# Flow_sensor.net
KiCad netlist of a schematic drawn in Altium Designer
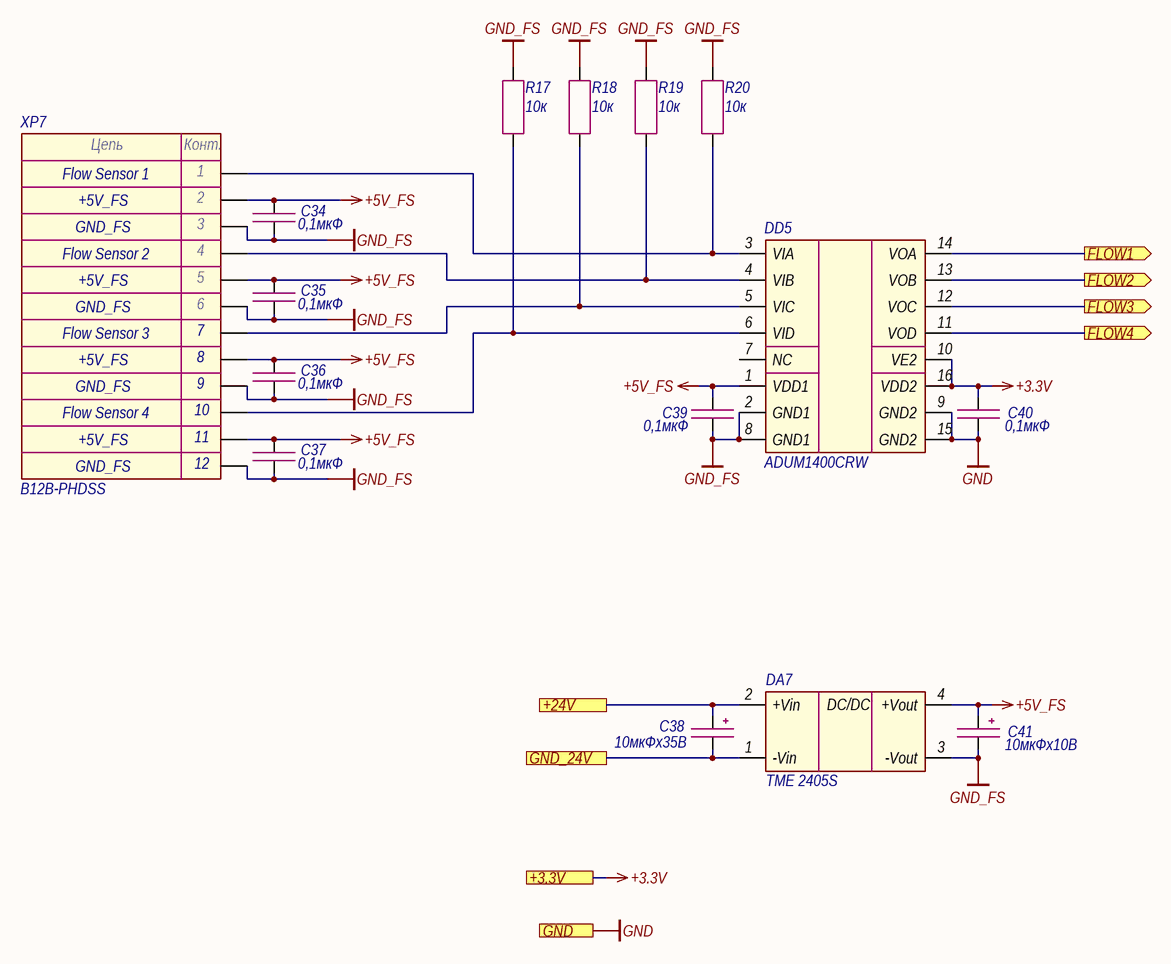
[diagram p0: Flow_sensor.SchDoc]

(export (version "E")
  (design (tool "Eeschema 10.0.6"))
  (components
    (comp (ref "C34")
      (value "0,1мкФ")
      (footprint "Pcb_library:CAP_0603")
      (fields (field (name "MANUFACTURER") "Murata"))
      (libsource (lib "Schem_library") (part "Capacitor"))
    )
    (comp (ref "C35")
      (value "0,1мкФ")
      (footprint "Pcb_library:CAP_0603")
      (fields (field (name "MANUFACTURER") "Murata"))
      (libsource (lib "Schem_library") (part "Capacitor"))
    )
    (comp (ref "C36")
      (value "0,1мкФ")
      (footprint "Pcb_library:CAP_0603")
      (fields (field (name "MANUFACTURER") "Murata"))
      (libsource (lib "Schem_library") (part "Capacitor"))
    )
    (comp (ref "C37")
      (value "0,1мкФ")
      (footprint "Pcb_library:CAP_0603")
      (fields (field (name "MANUFACTURER") "Murata"))
      (libsource (lib "Schem_library") (part "Capacitor"))
    )
    (comp (ref "C38")
      (value "10мкФх35B")
      (footprint "Pcb_library:CAP_C")
      (libsource (lib "Schem_library") (part "Capacitor_Polar"))
    )
    (comp (ref "C39")
      (value "0,1мкФ")
      (footprint "Pcb_library:CAP_0603")
      (fields (field (name "MANUFACTURER") "Murata"))
      (libsource (lib "Schem_library") (part "Capacitor"))
    )
    (comp (ref "C40")
      (value "0,1мкФ")
      (footprint "Pcb_library:CAP_0603")
      (fields (field (name "MANUFACTURER") "Murata"))
      (libsource (lib "Schem_library") (part "Capacitor"))
    )
    (comp (ref "C41")
      (value "10мкФх10B")
      (footprint "Pcb_library:CAP_A")
      (libsource (lib "Schem_library") (part "Capacitor_Polar"))
    )
    (comp (ref "DA7")
      (value "TME 2405S")
      (footprint "Pcb_library:TME (SIP-4)")
      (fields (field (name "MANUFACTURER") "Traco Power"))
      (libsource (lib "Schem_library") (part "TME"))
    )
    (comp (ref "DD5")
      (value "ADUM1400CRW")
      (footprint "Pcb_library:SOIC-16W")
      (fields (field (name "MANUFACTURER") "Analog Devices"))
      (libsource (lib "Schem_library") (part "ADUM1400"))
    )
    (comp (ref "R17")
      (value "10к")
      (footprint "Pcb_library:RES_0603")
      (fields (field (name "MANUFACTURER") "Yageo"))
      (libsource (lib "Schem_library") (part "Resistor"))
    )
    (comp (ref "R18")
      (value "10к")
      (footprint "Pcb_library:RES_0603")
      (fields (field (name "MANUFACTURER") "Yageo"))
      (libsource (lib "Schem_library") (part "Resistor"))
    )
    (comp (ref "R19")
      (value "10к")
      (footprint "Pcb_library:RES_0603")
      (fields (field (name "MANUFACTURER") "Yageo"))
      (libsource (lib "Schem_library") (part "Resistor"))
    )
    (comp (ref "R20")
      (value "10к")
      (footprint "Pcb_library:RES_0603")
      (fields (field (name "MANUFACTURER") "Yageo"))
      (libsource (lib "Schem_library") (part "Resistor"))
    )
    (comp (ref "XP7")
      (value "B12B-PHDSS")
      (footprint "Pcb_library:B12B-PHDSS")
      (fields (field (name "MANUFACTURER") "JST"))
      (libsource (lib "Schem_library") (part "Connector-12"))
    )
  )
  (nets
    (net (code "1") (name "+3.3V") (class "Default")
      (node (ref "C40") (pin "1") (pinfunction "1_1") (pintype "passive"))
      (node (ref "DD5") (pin "10") (pinfunction "VE2_10") (pintype "passive"))
      (node (ref "DD5") (pin "16") (pinfunction "VDD2_16") (pintype "passive"))
    )
    (net (code "2") (name "+5V_FS") (class "Default")
      (node (ref "C34") (pin "1") (pinfunction "1_1") (pintype "passive"))
      (node (ref "C35") (pin "1") (pinfunction "1_1") (pintype "passive"))
      (node (ref "C36") (pin "1") (pinfunction "1_1") (pintype "passive"))
      (node (ref "C37") (pin "1") (pinfunction "1_1") (pintype "passive"))
      (node (ref "C39") (pin "1") (pinfunction "1_1") (pintype "passive"))
      (node (ref "C41") (pin "1") (pinfunction "1_1") (pintype "passive"))
      (node (ref "DA7") (pin "4") (pinfunction "+Vout_4") (pintype "passive"))
      (node (ref "DD5") (pin "1") (pinfunction "VDD1_1") (pintype "passive"))
      (node (ref "XP7") (pin "11") (pintype "passive"))
      (node (ref "XP7") (pin "2") (pintype "passive"))
      (node (ref "XP7") (pin "5") (pintype "passive"))
      (node (ref "XP7") (pin "8") (pintype "passive"))
    )
    (net (code "3") (name "/+24V") (class "Default")
      (node (ref "C38") (pin "1") (pinfunction "1_1") (pintype "passive"))
      (node (ref "DA7") (pin "2") (pinfunction "+Vin_2") (pintype "passive"))
    )
    (net (code "4") (name "/FLOW1") (class "Default")
      (node (ref "DD5") (pin "14") (pinfunction "VOA_14") (pintype "passive"))
    )
    (net (code "5") (name "/FLOW2") (class "Default")
      (node (ref "DD5") (pin "13") (pinfunction "VOB_13") (pintype "passive"))
    )
    (net (code "6") (name "/FLOW3") (class "Default")
      (node (ref "DD5") (pin "12") (pinfunction "VOC_12") (pintype "passive"))
    )
    (net (code "7") (name "/FLOW4") (class "Default")
      (node (ref "DD5") (pin "11") (pinfunction "VOD_11") (pintype "passive"))
    )
    (net (code "8") (name "/GND_24V") (class "Default")
      (node (ref "C38") (pin "2") (pinfunction "2_2") (pintype "passive"))
      (node (ref "DA7") (pin "1") (pinfunction "-Vin_1") (pintype "passive"))
    )
    (net (code "9") (name "GND") (class "Default")
      (node (ref "C40") (pin "2") (pinfunction "2_2") (pintype "passive"))
      (node (ref "DD5") (pin "15") (pinfunction "GND2_15") (pintype "passive"))
      (node (ref "DD5") (pin "9") (pinfunction "GND2_9") (pintype "passive"))
    )
    (net (code "10") (name "GND_FS") (class "Default")
      (node (ref "C34") (pin "2") (pinfunction "2_2") (pintype "passive"))
      (node (ref "C35") (pin "2") (pinfunction "2_2") (pintype "passive"))
      (node (ref "C36") (pin "2") (pinfunction "2_2") (pintype "passive"))
      (node (ref "C37") (pin "2") (pinfunction "2_2") (pintype "passive"))
      (node (ref "C39") (pin "2") (pinfunction "2_2") (pintype "passive"))
      (node (ref "C41") (pin "2") (pinfunction "2_2") (pintype "passive"))
      (node (ref "DA7") (pin "3") (pinfunction "-Vout_3") (pintype "passive"))
      (node (ref "DD5") (pin "2") (pinfunction "GND1_2") (pintype "passive"))
      (node (ref "DD5") (pin "8") (pinfunction "GND1_8") (pintype "passive"))
      (node (ref "R17") (pin "2") (pinfunction "2_2") (pintype "passive"))
      (node (ref "R18") (pin "2") (pinfunction "2_2") (pintype "passive"))
      (node (ref "R19") (pin "2") (pinfunction "2_2") (pintype "passive"))
      (node (ref "R20") (pin "2") (pinfunction "2_2") (pintype "passive"))
      (node (ref "XP7") (pin "12") (pintype "passive"))
      (node (ref "XP7") (pin "3") (pintype "passive"))
      (node (ref "XP7") (pin "6") (pintype "passive"))
      (node (ref "XP7") (pin "9") (pintype "passive"))
    )
    (net (code "11") (name "Net-(DD5-VIA)") (class "Default")
      (node (ref "DD5") (pin "3") (pinfunction "VIA_3") (pintype "passive"))
      (node (ref "R20") (pin "1") (pinfunction "1_1") (pintype "passive"))
      (node (ref "XP7") (pin "1") (pintype "passive"))
    )
    (net (code "12") (name "Net-(DD5-VIB)") (class "Default")
      (node (ref "DD5") (pin "4") (pinfunction "VIB_4") (pintype "passive"))
      (node (ref "R19") (pin "1") (pinfunction "1_1") (pintype "passive"))
      (node (ref "XP7") (pin "4") (pintype "passive"))
    )
    (net (code "13") (name "Net-(DD5-VIC)") (class "Default")
      (node (ref "DD5") (pin "5") (pinfunction "VIC_5") (pintype "passive"))
      (node (ref "R18") (pin "1") (pinfunction "1_1") (pintype "passive"))
      (node (ref "XP7") (pin "7") (pintype "passive"))
    )
    (net (code "14") (name "Net-(DD5-VID)") (class "Default")
      (node (ref "DD5") (pin "6") (pinfunction "VID_6") (pintype "passive"))
      (node (ref "R17") (pin "1") (pinfunction "1_1") (pintype "passive"))
      (node (ref "XP7") (pin "10") (pintype "passive"))
    )
    (net (code "15") (name "unconnected-(DD5-NC-Pad7)") (class "Default")
      (node (ref "DD5") (pin "7") (pinfunction "NC_7") (pintype "passive"))
    )
  )
)
